# Circuit_Schematic.net
KiCad netlist of a schematic drawn in EAGLE
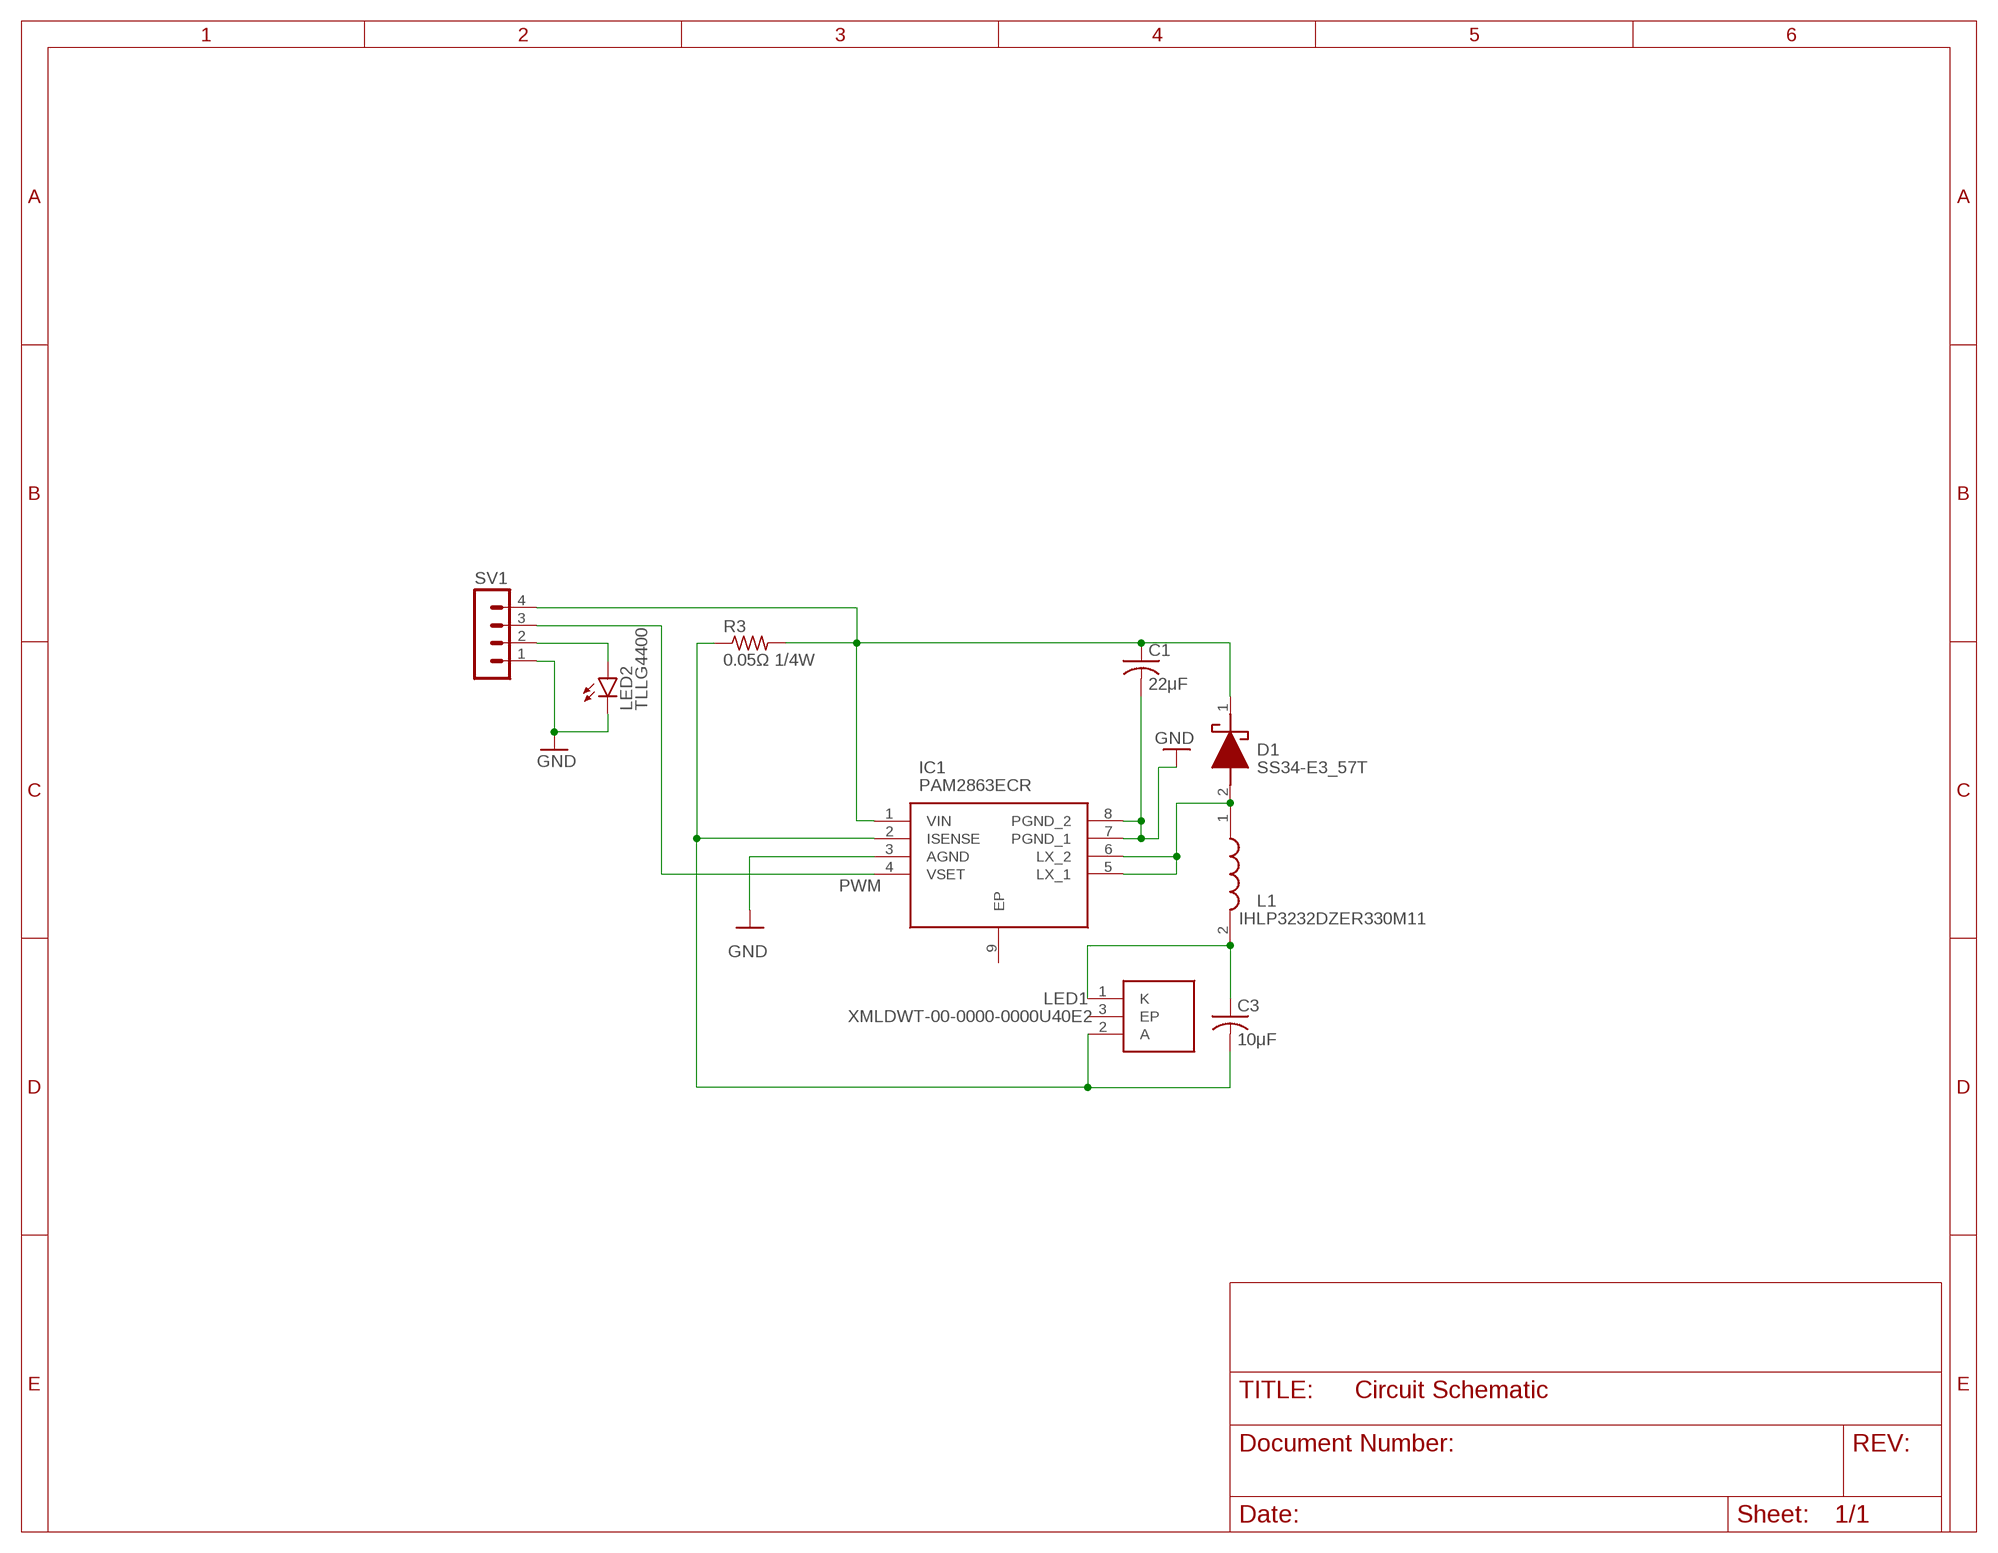
[diagram p0: schematic, sheet 1]

(export (version "E")
  (design (tool "Eeschema 10.0.6"))
  (components
    (comp (ref "C1")
      (value "22μF")
      (footprint "eagle-import:C1210")
      (libsource (lib "eagle-import") (part "C-USC1210"))
    )
    (comp (ref "C3")
      (value "10μF")
      (footprint "eagle-import:C1210")
      (libsource (lib "eagle-import") (part "C-USC1210"))
    )
    (comp (ref "D1")
      (value "SS34-E3_57T")
      (footprint "eagle-import:DIOM7959X262N")
      (fields
        (field (name "MANUFACTURER_PART_NUMBER") "SS34-E3/57T")
        (field (name "MOUSER_PART_NUMBER") "625-SS34-E3")
      )
      (libsource (lib "eagle-import") (part "SS34-E3_57T"))
    )
    (comp (ref "IC1")
      (value "PAM2863ECR")
      (footprint "eagle-import:SOIC127P600X175-9N")
      (fields (field (name "MOUSER_PART_NUMBER") "621-PAM2863ECR"))
      (libsource (lib "eagle-import") (part "PAM2863ECR"))
    )
    (comp (ref "L1")
      (value "IHLP3232DZER330M11")
      (footprint "eagle-import:IHLP3232DZER330M11")
      (fields (field (name "MOUSER_PART_NUMBER") "70-IHLP3232DZER330M1"))
      (libsource (lib "eagle-import") (part "IHLP3232DZER330M11"))
    )
    (comp (ref "LED1")
      (value "XMLDWT-00-0000-0000U40E2")
      (footprint "eagle-import:XMLDWT0000000000U40E2")
      (fields (field (name "MOUSER_PART_NUMBER") "941-XMLDWT0000U40E2"))
      (libsource (lib "eagle-import") (part "XMLDWT-00-0000-0000U40E2"))
    )
    (comp (ref "LED2")
      (value "TLLG4400")
      (footprint "eagle-import:LED3MM")
      (fields (field (name "MF") "VISHAY SEMICONDUCTOR"))
      (libsource (lib "eagle-import") (part "TLLG4400"))
    )
    (comp (ref "R3")
      (value "0.05Ω 1/4W")
      (footprint "eagle-import:R0805")
      (libsource (lib "eagle-import") (part "R-US_R0805"))
    )
    (comp (ref "SV1")
      (value "MA04-1")
      (footprint "eagle-import:MA04-1")
      (libsource (lib "eagle-import") (part "MA04-1"))
    )
  )
  (nets
    (net (code "1") (name "GND") (class "Default")
      (node (ref "C1") (pin "2") (pinfunction "2_2") (pintype "passive"))
      (node (ref "IC1") (pin "3") (pinfunction "AGND_3") (pintype "bidirectional"))
      (node (ref "IC1") (pin "7") (pinfunction "PGND_1_7") (pintype "bidirectional"))
      (node (ref "IC1") (pin "8") (pinfunction "PGND_2_8") (pintype "bidirectional"))
      (node (ref "LED2") (pin "K") (pinfunction "C_K") (pintype "passive"))
      (node (ref "SV1") (pin "1") (pinfunction "1_1") (pintype "passive"))
    )
    (net (code "2") (name "Net-(D1-A)") (class "Default")
      (node (ref "D1") (pin "2") (pinfunction "A_2") (pintype "bidirectional"))
      (node (ref "IC1") (pin "5") (pinfunction "LX_1_5") (pintype "bidirectional"))
      (node (ref "IC1") (pin "6") (pinfunction "LX_2_6") (pintype "bidirectional"))
      (node (ref "L1") (pin "1") (pinfunction "1_1") (pintype "bidirectional"))
    )
    (net (code "3") (name "Net-(D1-K)") (class "Default")
      (node (ref "C1") (pin "1") (pinfunction "1_1") (pintype "passive"))
      (node (ref "D1") (pin "1") (pinfunction "K_1") (pintype "bidirectional"))
      (node (ref "IC1") (pin "1") (pinfunction "VIN_1") (pintype "bidirectional"))
      (node (ref "R3") (pin "2") (pinfunction "2_2") (pintype "passive"))
      (node (ref "SV1") (pin "4") (pinfunction "4_4") (pintype "passive"))
    )
    (net (code "4") (name "Net-(IC1-ISENSE)") (class "Default")
      (node (ref "C3") (pin "2") (pinfunction "2_2") (pintype "passive"))
      (node (ref "IC1") (pin "2") (pinfunction "ISENSE_2") (pintype "bidirectional"))
      (node (ref "LED1") (pin "2") (pinfunction "A_2") (pintype "bidirectional"))
      (node (ref "R3") (pin "1") (pinfunction "1_1") (pintype "passive"))
    )
    (net (code "5") (name "Net-(IC1-VSET)") (class "Default")
      (node (ref "IC1") (pin "4") (pinfunction "VSET_4") (pintype "bidirectional"))
      (node (ref "SV1") (pin "3") (pinfunction "3_3") (pintype "passive"))
    )
    (net (code "6") (name "Net-(LED1-K)") (class "Default")
      (node (ref "C3") (pin "1") (pinfunction "1_1") (pintype "passive"))
      (node (ref "L1") (pin "2") (pinfunction "2_2") (pintype "bidirectional"))
      (node (ref "LED1") (pin "1") (pinfunction "K_1") (pintype "bidirectional"))
    )
    (net (code "7") (name "Net-(LED2-PadA)") (class "Default")
      (node (ref "LED2") (pin "A") (pinfunction "A_A") (pintype "passive"))
      (node (ref "SV1") (pin "2") (pinfunction "2_2") (pintype "passive"))
    )
    (net (code "8") (name "unconnected-(IC1-EP-Pad9)") (class "Default")
      (node (ref "IC1") (pin "9") (pinfunction "EP_9") (pintype "bidirectional"))
    )
    (net (code "9") (name "unconnected-(LED1-EP-Pad3)") (class "Default")
      (node (ref "LED1") (pin "3") (pinfunction "EP_3") (pintype "bidirectional"))
    )
  )
)
